# PDB.net
KiCad netlist of a schematic drawn in EAGLE
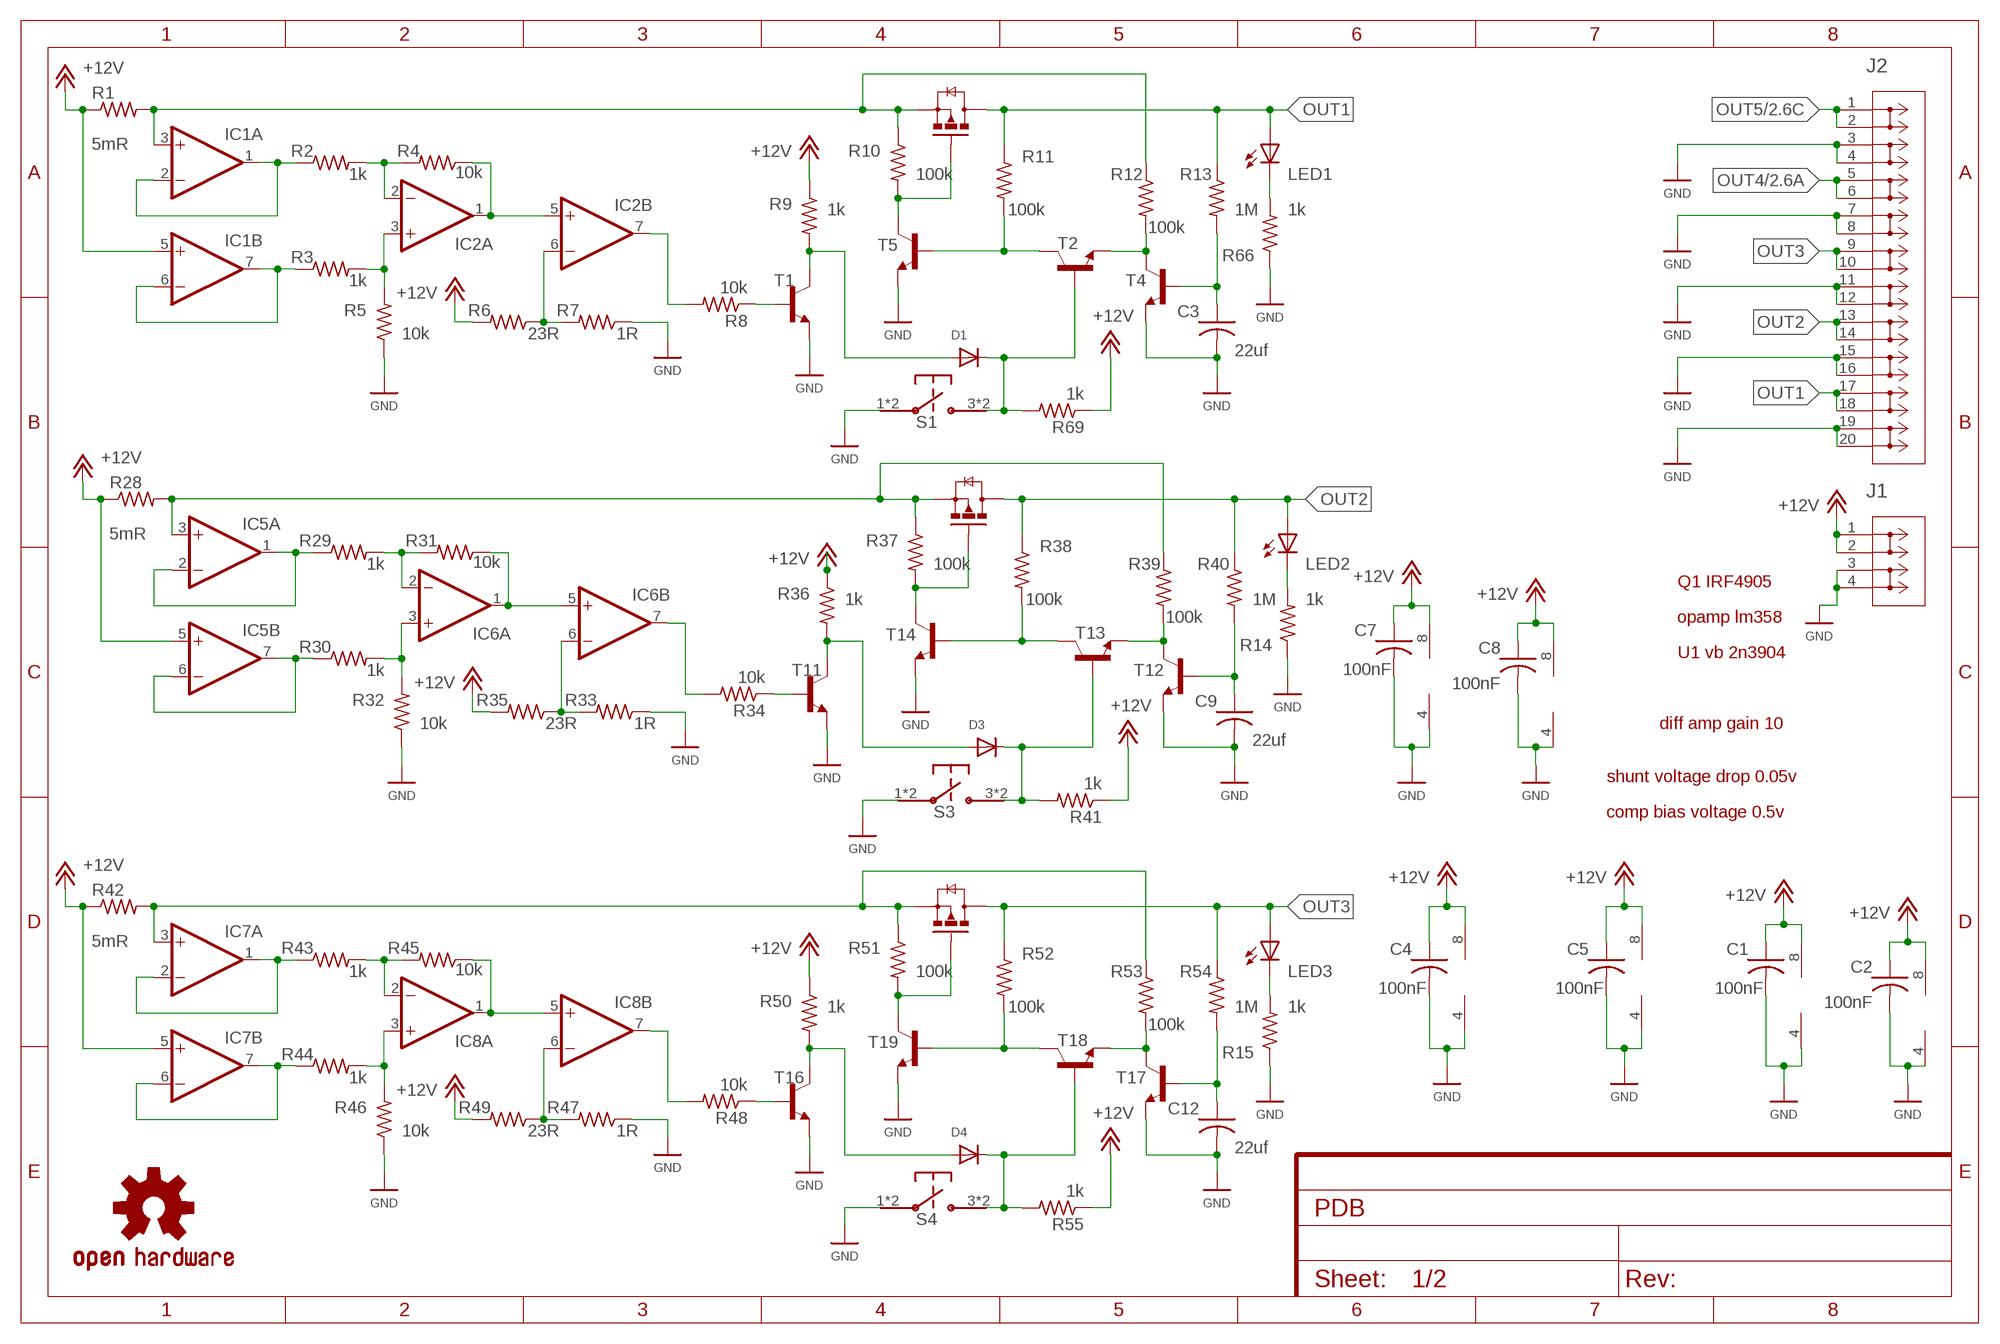
[diagram p0: schematic, sheet 1]
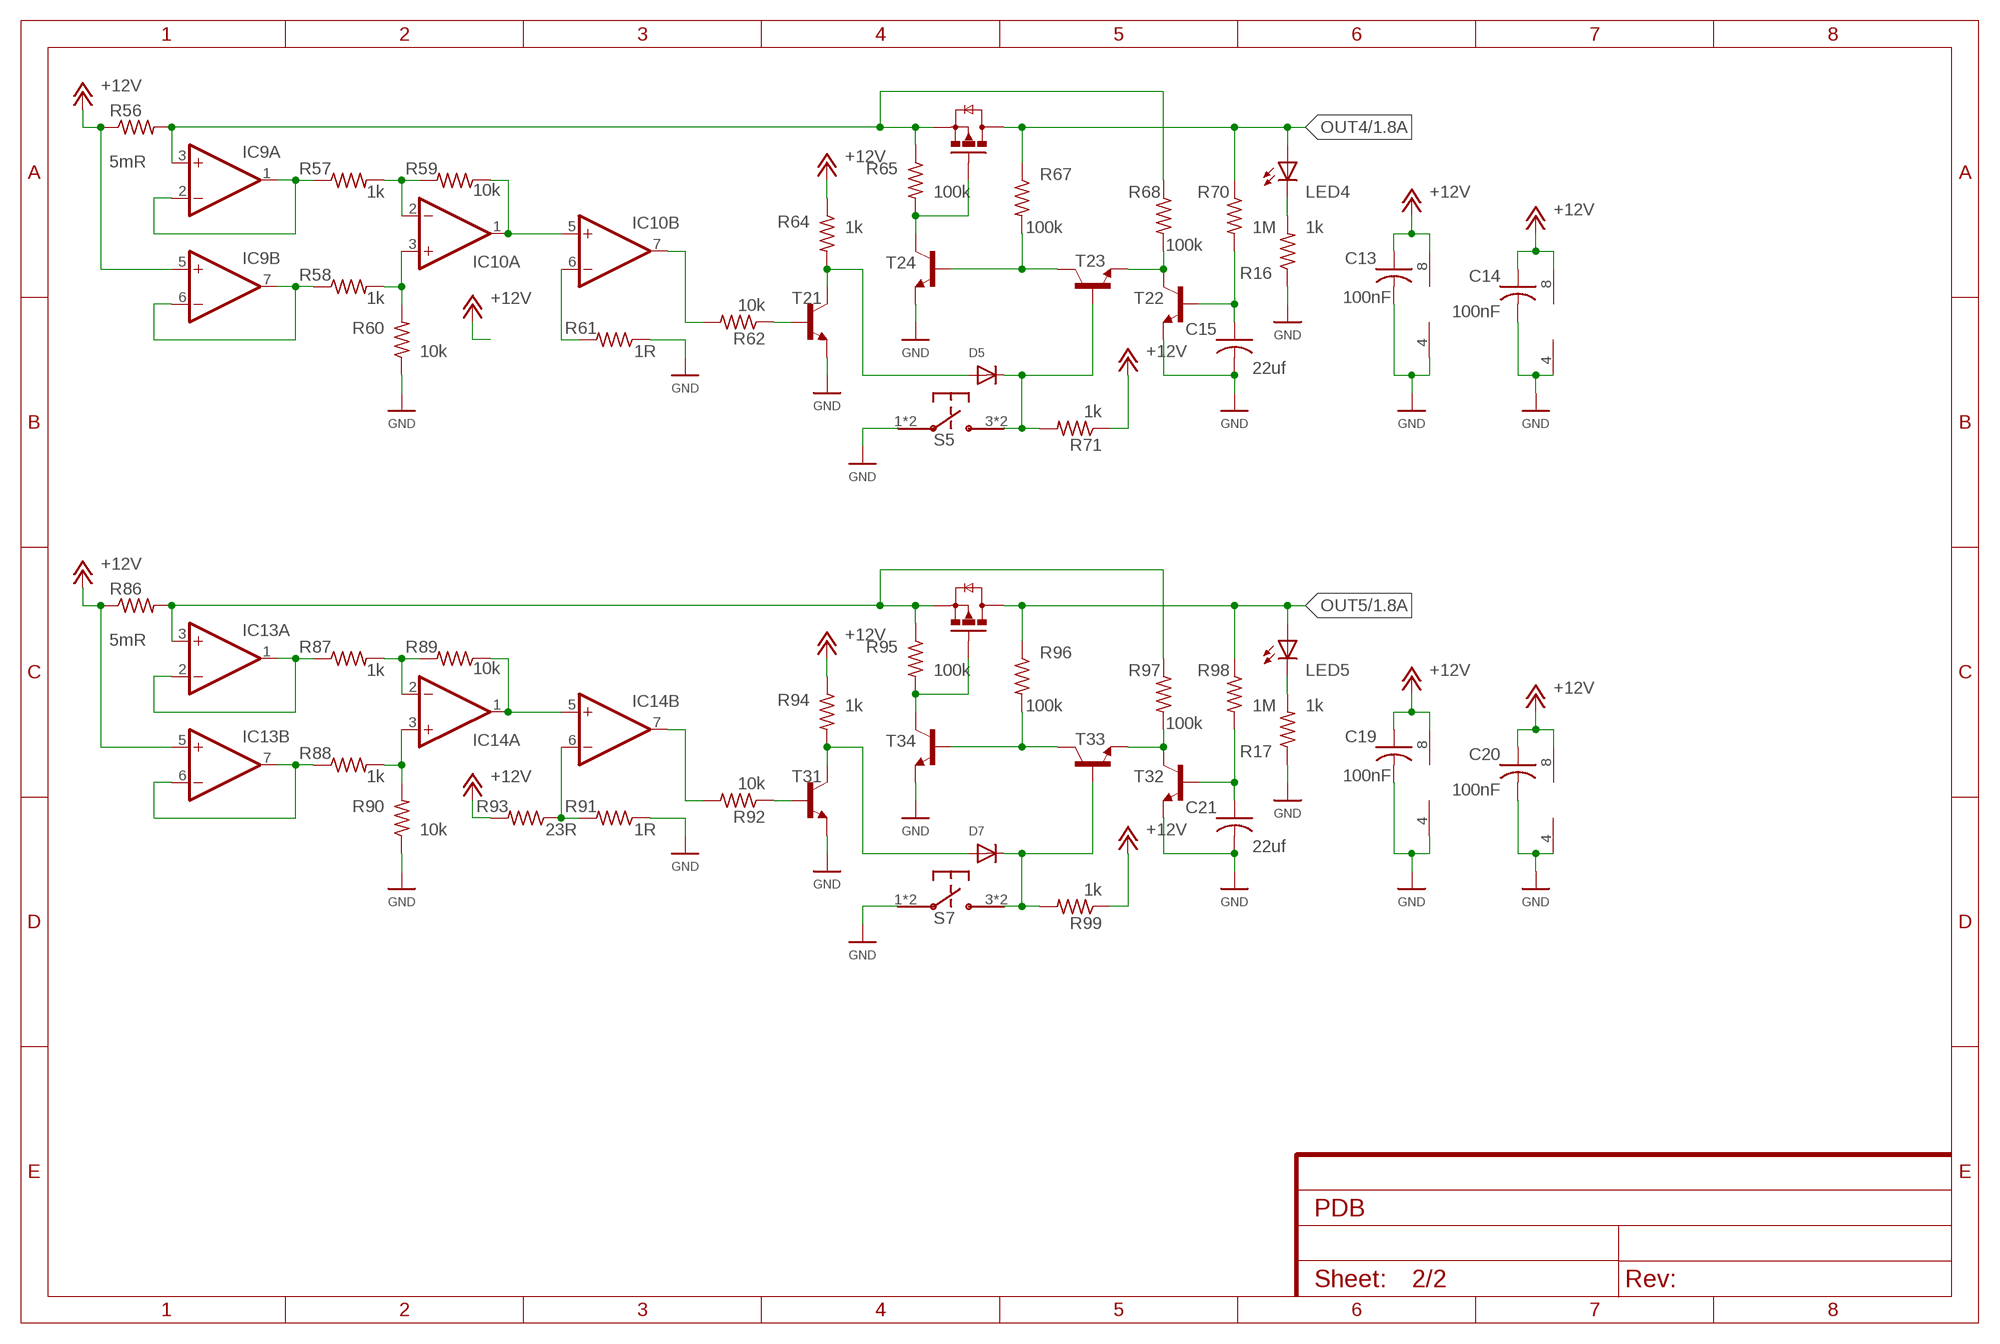
[diagram p1: schematic, sheet 2]

(export (version "E")
  (design (tool "Eeschema 10.0.6"))
  (components
    (comp (ref "C13")
      (value "100nF")
      (footprint "eagle-import:C0603")
      (libsource (lib "eagle-import") (part "C-USC0603"))
    )
    (comp (ref "C14")
      (value "100nF")
      (footprint "eagle-import:C0603")
      (libsource (lib "eagle-import") (part "C-USC0603"))
    )
    (comp (ref "C15")
      (value "22uf")
      (footprint "eagle-import:C0805")
      (libsource (lib "eagle-import") (part "C-USC0805"))
    )
    (comp (ref "C19")
      (value "100nF")
      (footprint "eagle-import:C0603")
      (libsource (lib "eagle-import") (part "C-USC0603"))
    )
    (comp (ref "C20")
      (value "100nF")
      (footprint "eagle-import:C0603")
      (libsource (lib "eagle-import") (part "C-USC0603"))
    )
    (comp (ref "C21")
      (value "22uf")
      (footprint "eagle-import:C0805")
      (libsource (lib "eagle-import") (part "C-USC0805"))
    )
    (comp (ref "D5")
      (value "DIODESOD-323F")
      (footprint "eagle-import:SOD-323F")
      (libsource (lib "eagle-import") (part "DIODESOD-323F"))
    )
    (comp (ref "D7")
      (value "DIODESOD-323F")
      (footprint "eagle-import:SOD-323F")
      (libsource (lib "eagle-import") (part "DIODESOD-323F"))
    )
    (comp (ref "IC9")
      (value "LM358D")
      (footprint "eagle-import:SO08")
      (libsource (lib "eagle-import") (part "LM358D"))
    )
    (comp (ref "IC10")
      (value "LM358D")
      (footprint "eagle-import:SO08")
      (libsource (lib "eagle-import") (part "LM358D"))
    )
    (comp (ref "IC13")
      (value "LM358D")
      (footprint "eagle-import:SO08")
      (libsource (lib "eagle-import") (part "LM358D"))
    )
    (comp (ref "IC14")
      (value "LM358D")
      (footprint "eagle-import:SO08")
      (libsource (lib "eagle-import") (part "LM358D"))
    )
    (comp (ref "LED4")
      (value "LEDCHIP-LED0603")
      (footprint "eagle-import:CHIP-LED0603")
      (libsource (lib "eagle-import") (part "LEDCHIP-LED0603"))
    )
    (comp (ref "LED5")
      (value "LEDCHIP-LED0603")
      (footprint "eagle-import:CHIP-LED0603")
      (libsource (lib "eagle-import") (part "LEDCHIP-LED0603"))
    )
    (comp (ref "R16")
      (value "1k")
      (footprint "eagle-import:R0603")
      (libsource (lib "eagle-import") (part "R-US_R0603"))
    )
    (comp (ref "R17")
      (value "1k")
      (footprint "eagle-import:R0603")
      (libsource (lib "eagle-import") (part "R-US_R0603"))
    )
    (comp (ref "R56")
      (value "5mR")
      (footprint "eagle-import:R2512")
      (libsource (lib "eagle-import") (part "R-US_R2512"))
    )
    (comp (ref "R57")
      (value "1k")
      (footprint "eagle-import:R0603")
      (libsource (lib "eagle-import") (part "R-US_R0603"))
    )
    (comp (ref "R58")
      (value "1k")
      (footprint "eagle-import:R0603")
      (libsource (lib "eagle-import") (part "R-US_R0603"))
    )
    (comp (ref "R59")
      (value "10k")
      (footprint "eagle-import:R0603")
      (libsource (lib "eagle-import") (part "R-US_R0603"))
    )
    (comp (ref "R60")
      (value "10k")
      (footprint "eagle-import:R0603")
      (libsource (lib "eagle-import") (part "R-US_R0603"))
    )
    (comp (ref "R61")
      (value "1R")
      (footprint "eagle-import:R0603")
      (libsource (lib "eagle-import") (part "R-US_R0603"))
    )
    (comp (ref "R62")
      (value "10k")
      (footprint "eagle-import:R0603")
      (libsource (lib "eagle-import") (part "R-US_R0603"))
    )
    (comp (ref "R64")
      (value "1k")
      (footprint "eagle-import:R0603")
      (libsource (lib "eagle-import") (part "R-US_R0603"))
    )
    (comp (ref "R65")
      (value "100k")
      (footprint "eagle-import:R0603")
      (libsource (lib "eagle-import") (part "R-US_R0603"))
    )
    (comp (ref "R67")
      (value "100k")
      (footprint "eagle-import:R0603")
      (libsource (lib "eagle-import") (part "R-US_R0603"))
    )
    (comp (ref "R68")
      (value "100k")
      (footprint "eagle-import:R0603")
      (libsource (lib "eagle-import") (part "R-US_R0603"))
    )
    (comp (ref "R70")
      (value "1M")
      (footprint "eagle-import:R0603")
      (libsource (lib "eagle-import") (part "R-US_R0603"))
    )
    (comp (ref "R71")
      (value "1k")
      (footprint "eagle-import:R0603")
      (libsource (lib "eagle-import") (part "R-US_R0603"))
    )
    (comp (ref "R86")
      (value "5mR")
      (footprint "eagle-import:R2512")
      (libsource (lib "eagle-import") (part "R-US_R2512"))
    )
    (comp (ref "R87")
      (value "1k")
      (footprint "eagle-import:R0603")
      (libsource (lib "eagle-import") (part "R-US_R0603"))
    )
    (comp (ref "R88")
      (value "1k")
      (footprint "eagle-import:R0603")
      (libsource (lib "eagle-import") (part "R-US_R0603"))
    )
    (comp (ref "R89")
      (value "10k")
      (footprint "eagle-import:R0603")
      (libsource (lib "eagle-import") (part "R-US_R0603"))
    )
    (comp (ref "R90")
      (value "10k")
      (footprint "eagle-import:R0603")
      (libsource (lib "eagle-import") (part "R-US_R0603"))
    )
    (comp (ref "R91")
      (value "1R")
      (footprint "eagle-import:R0603")
      (libsource (lib "eagle-import") (part "R-US_R0603"))
    )
    (comp (ref "R92")
      (value "10k")
      (footprint "eagle-import:R0603")
      (libsource (lib "eagle-import") (part "R-US_R0603"))
    )
    (comp (ref "R93")
      (value "23R")
      (footprint "eagle-import:R0603")
      (libsource (lib "eagle-import") (part "R-US_R0603"))
    )
    (comp (ref "R94")
      (value "1k")
      (footprint "eagle-import:R0603")
      (libsource (lib "eagle-import") (part "R-US_R0603"))
    )
    (comp (ref "R95")
      (value "100k")
      (footprint "eagle-import:R0603")
      (libsource (lib "eagle-import") (part "R-US_R0603"))
    )
    (comp (ref "R96")
      (value "100k")
      (footprint "eagle-import:R0603")
      (libsource (lib "eagle-import") (part "R-US_R0603"))
    )
    (comp (ref "R97")
      (value "100k")
      (footprint "eagle-import:R0603")
      (libsource (lib "eagle-import") (part "R-US_R0603"))
    )
    (comp (ref "R98")
      (value "1M")
      (footprint "eagle-import:R0603")
      (libsource (lib "eagle-import") (part "R-US_R0603"))
    )
    (comp (ref "R99")
      (value "1k")
      (footprint "eagle-import:R0603")
      (libsource (lib "eagle-import") (part "R-US_R0603"))
    )
    (comp (ref "S5")
      (value "PTS645SM43SMTR")
      (footprint "eagle-import:PTS645SM43SMTR")
      (libsource (lib "eagle-import") (part "PTS645SM43SMTR"))
    )
    (comp (ref "S7")
      (value "PTS645SM43SMTR")
      (footprint "eagle-import:PTS645SM43SMTR")
      (libsource (lib "eagle-import") (part "PTS645SM43SMTR"))
    )
    (comp (ref "T21")
      (value "2N3904SMD")
      (footprint "eagle-import:SOT23-BACKUP")
      (libsource (lib "eagle-import") (part "2N3904SMD"))
    )
    (comp (ref "T22")
      (value "2N3904SMD")
      (footprint "eagle-import:SOT23-BACKUP")
      (libsource (lib "eagle-import") (part "2N3904SMD"))
    )
    (comp (ref "T23")
      (value "2N3904SMD")
      (footprint "eagle-import:SOT23-BACKUP")
      (libsource (lib "eagle-import") (part "2N3904SMD"))
    )
    (comp (ref "T24")
      (value "2N3904SMD")
      (footprint "eagle-import:SOT23-BACKUP")
      (libsource (lib "eagle-import") (part "2N3904SMD"))
    )
    (comp (ref "T25")
      (value "IRF4905")
      (footprint "eagle-import:TO263-3")
      (libsource (lib "eagle-import") (part "IRF4905"))
    )
    (comp (ref "T31")
      (value "2N3904SMD")
      (footprint "eagle-import:SOT23-BACKUP")
      (libsource (lib "eagle-import") (part "2N3904SMD"))
    )
    (comp (ref "T32")
      (value "2N3904SMD")
      (footprint "eagle-import:SOT23-BACKUP")
      (libsource (lib "eagle-import") (part "2N3904SMD"))
    )
    (comp (ref "T33")
      (value "2N3904SMD")
      (footprint "eagle-import:SOT23-BACKUP")
      (libsource (lib "eagle-import") (part "2N3904SMD"))
    )
    (comp (ref "T34")
      (value "2N3904SMD")
      (footprint "eagle-import:SOT23-BACKUP")
      (libsource (lib "eagle-import") (part "2N3904SMD"))
    )
    (comp (ref "T35")
      (value "IRF4905")
      (footprint "eagle-import:TO263-3")
      (libsource (lib "eagle-import") (part "IRF4905"))
    )
    (comp (ref "C1")
      (value "100nF")
      (footprint "eagle-import:C0603")
      (libsource (lib "eagle-import") (part "C-USC0603"))
    )
    (comp (ref "C2")
      (value "100nF")
      (footprint "eagle-import:C0603")
      (libsource (lib "eagle-import") (part "C-USC0603"))
    )
    (comp (ref "C3")
      (value "22uf")
      (footprint "eagle-import:C0805")
      (libsource (lib "eagle-import") (part "C-USC0805"))
    )
    (comp (ref "C4")
      (value "100nF")
      (footprint "eagle-import:C0603")
      (libsource (lib "eagle-import") (part "C-USC0603"))
    )
    (comp (ref "C5")
      (value "100nF")
      (footprint "eagle-import:C0603")
      (libsource (lib "eagle-import") (part "C-USC0603"))
    )
    (comp (ref "C7")
      (value "100nF")
      (footprint "eagle-import:C0603")
      (libsource (lib "eagle-import") (part "C-USC0603"))
    )
    (comp (ref "C8")
      (value "100nF")
      (footprint "eagle-import:C0603")
      (libsource (lib "eagle-import") (part "C-USC0603"))
    )
    (comp (ref "C9")
      (value "22uf")
      (footprint "eagle-import:C0805")
      (libsource (lib "eagle-import") (part "C-USC0805"))
    )
    (comp (ref "C12")
      (value "22uf")
      (footprint "eagle-import:C0805")
      (libsource (lib "eagle-import") (part "C-USC0805"))
    )
    (comp (ref "D1")
      (value "DIODESOD-323F")
      (footprint "eagle-import:SOD-323F")
      (libsource (lib "eagle-import") (part "DIODESOD-323F"))
    )
    (comp (ref "D3")
      (value "DIODESOD-323F")
      (footprint "eagle-import:SOD-323F")
      (libsource (lib "eagle-import") (part "DIODESOD-323F"))
    )
    (comp (ref "D4")
      (value "DIODESOD-323F")
      (footprint "eagle-import:SOD-323F")
      (libsource (lib "eagle-import") (part "DIODESOD-323F"))
    )
    (comp (ref "IC1")
      (value "LM358D")
      (footprint "eagle-import:SO08")
      (libsource (lib "eagle-import") (part "LM358D"))
    )
    (comp (ref "IC2")
      (value "LM358D")
      (footprint "eagle-import:SO08")
      (libsource (lib "eagle-import") (part "LM358D"))
    )
    (comp (ref "IC5")
      (value "LM358D")
      (footprint "eagle-import:SO08")
      (libsource (lib "eagle-import") (part "LM358D"))
    )
    (comp (ref "IC6")
      (value "LM358D")
      (footprint "eagle-import:SO08")
      (libsource (lib "eagle-import") (part "LM358D"))
    )
    (comp (ref "IC7")
      (value "LM358D")
      (footprint "eagle-import:SO08")
      (libsource (lib "eagle-import") (part "LM358D"))
    )
    (comp (ref "IC8")
      (value "LM358D")
      (footprint "eagle-import:SO08")
      (libsource (lib "eagle-import") (part "LM358D"))
    )
    (comp (ref "J1")
      (value "2606-1102")
      (footprint "eagle-import:CONN2_2606-1102_WAG")
      (fields (field (name "COPYRIGHT") "Copyright (C) 2024 Ultra Librarian. All rights reserved."))
      (libsource (lib "eagle-import") (part "2606-1102"))
    )
    (comp (ref "J2")
      (value "2604-1110")
      (footprint "eagle-import:CONN10_2604-1110_WAG")
      (fields (field (name "COPYRIGHT") "Copyright (C) 2024 Ultra Librarian. All rights reserved."))
      (libsource (lib "eagle-import") (part "2604-1110"))
    )
    (comp (ref "LED1")
      (value "LEDCHIP-LED0603")
      (footprint "eagle-import:CHIP-LED0603")
      (libsource (lib "eagle-import") (part "LEDCHIP-LED0603"))
    )
    (comp (ref "LED2")
      (value "LEDCHIP-LED0603")
      (footprint "eagle-import:CHIP-LED0603")
      (libsource (lib "eagle-import") (part "LEDCHIP-LED0603"))
    )
    (comp (ref "LED3")
      (value "LEDCHIP-LED0603")
      (footprint "eagle-import:CHIP-LED0603")
      (libsource (lib "eagle-import") (part "LEDCHIP-LED0603"))
    )
    (comp (ref "LOGO1")
      (value "OSHW-LOGOL")
      (footprint "eagle-import:OSHW-LOGO-L")
      (libsource (lib "eagle-import") (part "OSHW-LOGOL"))
    )
    (comp (ref "R1")
      (value "5mR")
      (footprint "eagle-import:R2512")
      (libsource (lib "eagle-import") (part "R-US_R2512"))
    )
    (comp (ref "R2")
      (value "1k")
      (footprint "eagle-import:R0603")
      (libsource (lib "eagle-import") (part "R-US_R0603"))
    )
    (comp (ref "R3")
      (value "1k")
      (footprint "eagle-import:R0603")
      (libsource (lib "eagle-import") (part "R-US_R0603"))
    )
    (comp (ref "R4")
      (value "10k")
      (footprint "eagle-import:R0603")
      (libsource (lib "eagle-import") (part "R-US_R0603"))
    )
    (comp (ref "R5")
      (value "10k")
      (footprint "eagle-import:R0603")
      (libsource (lib "eagle-import") (part "R-US_R0603"))
    )
    (comp (ref "R6")
      (value "23R")
      (footprint "eagle-import:R0603")
      (libsource (lib "eagle-import") (part "R-US_R0603"))
    )
    (comp (ref "R7")
      (value "1R")
      (footprint "eagle-import:R0603")
      (libsource (lib "eagle-import") (part "R-US_R0603"))
    )
    (comp (ref "R8")
      (value "10k")
      (footprint "eagle-import:R0603")
      (libsource (lib "eagle-import") (part "R-US_R0603"))
    )
    (comp (ref "R9")
      (value "1k")
      (footprint "eagle-import:R0603")
      (libsource (lib "eagle-import") (part "R-US_R0603"))
    )
    (comp (ref "R10")
      (value "100k")
      (footprint "eagle-import:R0603")
      (libsource (lib "eagle-import") (part "R-US_R0603"))
    )
    (comp (ref "R11")
      (value "100k")
      (footprint "eagle-import:R0603")
      (libsource (lib "eagle-import") (part "R-US_R0603"))
    )
    (comp (ref "R12")
      (value "100k")
      (footprint "eagle-import:R0603")
      (libsource (lib "eagle-import") (part "R-US_R0603"))
    )
    (comp (ref "R13")
      (value "1M")
      (footprint "eagle-import:R0603")
      (libsource (lib "eagle-import") (part "R-US_R0603"))
    )
    (comp (ref "R14")
      (value "1k")
      (footprint "eagle-import:R0603")
      (libsource (lib "eagle-import") (part "R-US_R0603"))
    )
    (comp (ref "R15")
      (value "1k")
      (footprint "eagle-import:R0603")
      (libsource (lib "eagle-import") (part "R-US_R0603"))
    )
    (comp (ref "R28")
      (value "5mR")
      (footprint "eagle-import:R2512")
      (libsource (lib "eagle-import") (part "R-US_R2512"))
    )
    (comp (ref "R29")
      (value "1k")
      (footprint "eagle-import:R0603")
      (libsource (lib "eagle-import") (part "R-US_R0603"))
    )
    (comp (ref "R30")
      (value "1k")
      (footprint "eagle-import:R0603")
      (libsource (lib "eagle-import") (part "R-US_R0603"))
    )
    (comp (ref "R31")
      (value "10k")
      (footprint "eagle-import:R0603")
      (libsource (lib "eagle-import") (part "R-US_R0603"))
    )
    (comp (ref "R32")
      (value "10k")
      (footprint "eagle-import:R0603")
      (libsource (lib "eagle-import") (part "R-US_R0603"))
    )
    (comp (ref "R33")
      (value "1R")
      (footprint "eagle-import:R0603")
      (libsource (lib "eagle-import") (part "R-US_R0603"))
    )
    (comp (ref "R34")
      (value "10k")
      (footprint "eagle-import:R0603")
      (libsource (lib "eagle-import") (part "R-US_R0603"))
    )
    (comp (ref "R35")
      (value "23R")
      (footprint "eagle-import:R0603")
      (libsource (lib "eagle-import") (part "R-US_R0603"))
    )
    (comp (ref "R36")
      (value "1k")
      (footprint "eagle-import:R0603")
      (libsource (lib "eagle-import") (part "R-US_R0603"))
    )
    (comp (ref "R37")
      (value "100k")
      (footprint "eagle-import:R0603")
      (libsource (lib "eagle-import") (part "R-US_R0603"))
    )
    (comp (ref "R38")
      (value "100k")
      (footprint "eagle-import:R0603")
      (libsource (lib "eagle-import") (part "R-US_R0603"))
    )
    (comp (ref "R39")
      (value "100k")
      (footprint "eagle-import:R0603")
      (libsource (lib "eagle-import") (part "R-US_R0603"))
    )
    (comp (ref "R40")
      (value "1M")
      (footprint "eagle-import:R0603")
      (libsource (lib "eagle-import") (part "R-US_R0603"))
    )
    (comp (ref "R41")
      (value "1k")
      (footprint "eagle-import:R0603")
      (libsource (lib "eagle-import") (part "R-US_R0603"))
    )
    (comp (ref "R42")
      (value "5mR")
      (footprint "eagle-import:R2512")
      (libsource (lib "eagle-import") (part "R-US_R2512"))
    )
    (comp (ref "R43")
      (value "1k")
      (footprint "eagle-import:R0603")
      (libsource (lib "eagle-import") (part "R-US_R0603"))
    )
    (comp (ref "R44")
      (value "1k")
      (footprint "eagle-import:R0603")
      (libsource (lib "eagle-import") (part "R-US_R0603"))
    )
    (comp (ref "R45")
      (value "10k")
      (footprint "eagle-import:R0603")
      (libsource (lib "eagle-import") (part "R-US_R0603"))
    )
    (comp (ref "R46")
      (value "10k")
      (footprint "eagle-import:R0603")
      (libsource (lib "eagle-import") (part "R-US_R0603"))
    )
    (comp (ref "R47")
      (value "1R")
      (footprint "eagle-import:R0603")
      (libsource (lib "eagle-import") (part "R-US_R0603"))
    )
    (comp (ref "R48")
      (value "10k")
      (footprint "eagle-import:R0603")
      (libsource (lib "eagle-import") (part "R-US_R0603"))
    )
    (comp (ref "R49")
      (value "23R")
      (footprint "eagle-import:R0603")
      (libsource (lib "eagle-import") (part "R-US_R0603"))
    )
    (comp (ref "R50")
      (value "1k")
      (footprint "eagle-import:R0603")
      (libsource (lib "eagle-import") (part "R-US_R0603"))
    )
    (comp (ref "R51")
      (value "100k")
      (footprint "eagle-import:R0603")
      (libsource (lib "eagle-import") (part "R-US_R0603"))
    )
    (comp (ref "R52")
      (value "100k")
      (footprint "eagle-import:R0603")
      (libsource (lib "eagle-import") (part "R-US_R0603"))
    )
    (comp (ref "R53")
      (value "100k")
      (footprint "eagle-import:R0603")
      (libsource (lib "eagle-import") (part "R-US_R0603"))
    )
    (comp (ref "R54")
      (value "1M")
      (footprint "eagle-import:R0603")
      (libsource (lib "eagle-import") (part "R-US_R0603"))
    )
    (comp (ref "R55")
      (value "1k")
      (footprint "eagle-import:R0603")
      (libsource (lib "eagle-import") (part "R-US_R0603"))
    )
    (comp (ref "R66")
      (value "1k")
      (footprint "eagle-import:R0603")
      (libsource (lib "eagle-import") (part "R-US_R0603"))
    )
    (comp (ref "R69")
      (value "1k")
      (footprint "eagle-import:R0603")
      (libsource (lib "eagle-import") (part "R-US_R0603"))
    )
    (comp (ref "S1")
      (value "PTS645SM43SMTR")
      (footprint "eagle-import:PTS645SM43SMTR")
      (libsource (lib "eagle-import") (part "PTS645SM43SMTR"))
    )
    (comp (ref "S3")
      (value "PTS645SM43SMTR")
      (footprint "eagle-import:PTS645SM43SMTR")
      (libsource (lib "eagle-import") (part "PTS645SM43SMTR"))
    )
    (comp (ref "S4")
      (value "PTS645SM43SMTR")
      (footprint "eagle-import:PTS645SM43SMTR")
      (libsource (lib "eagle-import") (part "PTS645SM43SMTR"))
    )
    (comp (ref "T1")
      (value "2N3904SMD")
      (footprint "eagle-import:SOT23-BACKUP")
      (libsource (lib "eagle-import") (part "2N3904SMD"))
    )
    (comp (ref "T2")
      (value "2N3904SMD")
      (footprint "eagle-import:SOT23-BACKUP")
      (libsource (lib "eagle-import") (part "2N3904SMD"))
    )
    (comp (ref "T3")
      (value "IRF4905")
      (footprint "eagle-import:TO263-3")
      (libsource (lib "eagle-import") (part "IRF4905"))
    )
    (comp (ref "T4")
      (value "2N3904SMD")
      (footprint "eagle-import:SOT23-BACKUP")
      (libsource (lib "eagle-import") (part "2N3904SMD"))
    )
    (comp (ref "T5")
      (value "2N3904SMD")
      (footprint "eagle-import:SOT23-BACKUP")
      (libsource (lib "eagle-import") (part "2N3904SMD"))
    )
    (comp (ref "T11")
      (value "2N3904SMD")
      (footprint "eagle-import:SOT23-BACKUP")
      (libsource (lib "eagle-import") (part "2N3904SMD"))
    )
    (comp (ref "T12")
      (value "2N3904SMD")
      (footprint "eagle-import:SOT23-BACKUP")
      (libsource (lib "eagle-import") (part "2N3904SMD"))
    )
    (comp (ref "T13")
      (value "2N3904SMD")
      (footprint "eagle-import:SOT23-BACKUP")
      (libsource (lib "eagle-import") (part "2N3904SMD"))
    )
    (comp (ref "T14")
      (value "2N3904SMD")
      (footprint "eagle-import:SOT23-BACKUP")
      (libsource (lib "eagle-import") (part "2N3904SMD"))
    )
    (comp (ref "T15")
      (value "IRF4905")
      (footprint "eagle-import:TO263-3")
      (libsource (lib "eagle-import") (part "IRF4905"))
    )
    (comp (ref "T16")
      (value "2N3904SMD")
      (footprint "eagle-import:SOT23-BACKUP")
      (libsource (lib "eagle-import") (part "2N3904SMD"))
    )
    (comp (ref "T17")
      (value "2N3904SMD")
      (footprint "eagle-import:SOT23-BACKUP")
      (libsource (lib "eagle-import") (part "2N3904SMD"))
    )
    (comp (ref "T18")
      (value "2N3904SMD")
      (footprint "eagle-import:SOT23-BACKUP")
      (libsource (lib "eagle-import") (part "2N3904SMD"))
    )
    (comp (ref "T19")
      (value "2N3904SMD")
      (footprint "eagle-import:SOT23-BACKUP")
      (libsource (lib "eagle-import") (part "2N3904SMD"))
    )
    (comp (ref "T20")
      (value "IRF4905")
      (footprint "eagle-import:TO263-3")
      (libsource (lib "eagle-import") (part "IRF4905"))
    )
  )
  (nets
    (net (code "1") (name "+12V") (class "Default")
      (node (ref "C1") (pin "1") (pinfunction "1_1") (pintype "passive"))
      (node (ref "C13") (pin "1") (pinfunction "1_1") (pintype "passive"))
      (node (ref "C14") (pin "1") (pinfunction "1_1") (pintype "passive"))
      (node (ref "C19") (pin "1") (pinfunction "1_1") (pintype "passive"))
      (node (ref "C2") (pin "1") (pinfunction "1_1") (pintype "passive"))
      (node (ref "C20") (pin "1") (pinfunction "1_1") (pintype "passive"))
      (node (ref "C4") (pin "1") (pinfunction "1_1") (pintype "passive"))
      (node (ref "C5") (pin "1") (pinfunction "1_1") (pintype "passive"))
      (node (ref "C7") (pin "1") (pinfunction "1_1") (pintype "passive"))
      (node (ref "C8") (pin "1") (pinfunction "1_1") (pintype "passive"))
      (node (ref "IC1") (pin "5") (pinfunction "+IN_5") (pintype "input"))
      (node (ref "IC1") (pin "8") (pinfunction "V+_8") (pintype "power_in"))
      (node (ref "IC10") (pin "8") (pinfunction "V+_8") (pintype "power_in"))
      (node (ref "IC13") (pin "5") (pinfunction "+IN_5") (pintype "input"))
      (node (ref "IC13") (pin "8") (pinfunction "V+_8") (pintype "power_in"))
      (node (ref "IC14") (pin "8") (pinfunction "V+_8") (pintype "power_in"))
      (node (ref "IC2") (pin "8") (pinfunction "V+_8") (pintype "power_in"))
      (node (ref "IC5") (pin "5") (pinfunction "+IN_5") (pintype "input"))
      (node (ref "IC5") (pin "8") (pinfunction "V+_8") (pintype "power_in"))
      (node (ref "IC6") (pin "8") (pinfunction "V+_8") (pintype "power_in"))
      (node (ref "IC7") (pin "5") (pinfunction "+IN_5") (pintype "input"))
      (node (ref "IC7") (pin "8") (pinfunction "V+_8") (pintype "power_in"))
      (node (ref "IC8") (pin "8") (pinfunction "V+_8") (pintype "power_in"))
      (node (ref "IC9") (pin "5") (pinfunction "+IN_5") (pintype "input"))
      (node (ref "IC9") (pin "8") (pinfunction "V+_8") (pintype "power_in"))
      (node (ref "J1") (pin "1") (pinfunction "1_1_1") (pintype "passive"))
      (node (ref "J1") (pin "2") (pinfunction "1_2_2") (pintype "passive"))
      (node (ref "R1") (pin "1") (pinfunction "1_1") (pintype "passive"))
      (node (ref "R28") (pin "1") (pinfunction "1_1") (pintype "passive"))
      (node (ref "R35") (pin "2") (pinfunction "2_2") (pintype "passive"))
      (node (ref "R36") (pin "1") (pinfunction "1_1") (pintype "passive"))
      (node (ref "R41") (pin "1") (pinfunction "1_1") (pintype "passive"))
      (node (ref "R42") (pin "1") (pinfunction "1_1") (pintype "passive"))
      (node (ref "R49") (pin "2") (pinfunction "2_2") (pintype "passive"))
      (node (ref "R50") (pin "1") (pinfunction "1_1") (pintype "passive"))
      (node (ref "R55") (pin "1") (pinfunction "1_1") (pintype "passive"))
      (node (ref "R56") (pin "1") (pinfunction "1_1") (pintype "passive"))
      (node (ref "R6") (pin "2") (pinfunction "2_2") (pintype "passive"))
      (node (ref "R64") (pin "1") (pinfunction "1_1") (pintype "passive"))
      (node (ref "R69") (pin "1") (pinfunction "1_1") (pintype "passive"))
      (node (ref "R71") (pin "1") (pinfunction "1_1") (pintype "passive"))
      (node (ref "R86") (pin "1") (pinfunction "1_1") (pintype "passive"))
      (node (ref "R9") (pin "1") (pinfunction "1_1") (pintype "passive"))
      (node (ref "R93") (pin "2") (pinfunction "2_2") (pintype "passive"))
      (node (ref "R94") (pin "1") (pinfunction "1_1") (pintype "passive"))
      (node (ref "R99") (pin "1") (pinfunction "1_1") (pintype "passive"))
    )
    (net (code "2") (name "GND") (class "Default")
      (node (ref "C1") (pin "2") (pinfunction "2_2") (pintype "passive"))
      (node (ref "C12") (pin "2") (pinfunction "2_2") (pintype "passive"))
      (node (ref "C13") (pin "2") (pinfunction "2_2") (pintype "passive"))
      (node (ref "C14") (pin "2") (pinfunction "2_2") (pintype "passive"))
      (node (ref "C15") (pin "2") (pinfunction "2_2") (pintype "passive"))
      (node (ref "C19") (pin "2") (pinfunction "2_2") (pintype "passive"))
      (node (ref "C2") (pin "2") (pinfunction "2_2") (pintype "passive"))
      (node (ref "C20") (pin "2") (pinfunction "2_2") (pintype "passive"))
      (node (ref "C21") (pin "2") (pinfunction "2_2") (pintype "passive"))
      (node (ref "C3") (pin "2") (pinfunction "2_2") (pintype "passive"))
      (node (ref "C4") (pin "2") (pinfunction "2_2") (pintype "passive"))
      (node (ref "C5") (pin "2") (pinfunction "2_2") (pintype "passive"))
      (node (ref "C7") (pin "2") (pinfunction "2_2") (pintype "passive"))
      (node (ref "C8") (pin "2") (pinfunction "2_2") (pintype "passive"))
      (node (ref "C9") (pin "2") (pinfunction "2_2") (pintype "passive"))
      (node (ref "IC1") (pin "4") (pinfunction "V-_4") (pintype "power_in"))
      (node (ref "IC10") (pin "4") (pinfunction "V-_4") (pintype "power_in"))
      (node (ref "IC13") (pin "4") (pinfunction "V-_4") (pintype "power_in"))
      (node (ref "IC14") (pin "4") (pinfunction "V-_4") (pintype "power_in"))
      (node (ref "IC2") (pin "4") (pinfunction "V-_4") (pintype "power_in"))
      (node (ref "IC5") (pin "4") (pinfunction "V-_4") (pintype "power_in"))
      (node (ref "IC6") (pin "4") (pinfunction "V-_4") (pintype "power_in"))
      (node (ref "IC7") (pin "4") (pinfunction "V-_4") (pintype "power_in"))
      (node (ref "IC8") (pin "4") (pinfunction "V-_4") (pintype "power_in"))
      (node (ref "IC9") (pin "4") (pinfunction "V-_4") (pintype "power_in"))
      (node (ref "J1") (pin "3") (pinfunction "2_1_3") (pintype "passive"))
      (node (ref "J1") (pin "4") (pinfunction "2_2_4") (pintype "passive"))
      (node (ref "J2") (pin "11") (pinfunction "6_1_11") (pintype "passive"))
      (node (ref "J2") (pin "12") (pinfunction "6_2_12") (pintype "passive"))
      (node (ref "J2") (pin "15") (pinfunction "8_1_15") (pintype "passive"))
      (node (ref "J2") (pin "16") (pinfunction "8_2_16") (pintype "passive"))
      (node (ref "J2") (pin "19") (pinfunction "10_1_19") (pintype "passive"))
      (node (ref "J2") (pin "20") (pinfunction "10_2_20") (pintype "passive"))
      (node (ref "J2") (pin "3") (pinfunction "2_1_3") (pintype "passive"))
      (node (ref "J2") (pin "4") (pinfunction "2_2_4") (pintype "passive"))
      (node (ref "J2") (pin "7") (pinfunction "4_1_7") (pintype "passive"))
      (node (ref "J2") (pin "8") (pinfunction "4_2_8") (pintype "passive"))
      (node (ref "R14") (pin "1") (pinfunction "1_1") (pintype "passive"))
      (node (ref "R15") (pin "1") (pinfunction "1_1") (pintype "passive"))
      (node (ref "R16") (pin "1") (pinfunction "1_1") (pintype "passive"))
      (node (ref "R17") (pin "1") (pinfunction "1_1") (pintype "passive"))
      (node (ref "R32") (pin "1") (pinfunction "1_1") (pintype "passive"))
      (node (ref "R33") (pin "1") (pinfunction "1_1") (pintype "passive"))
      (node (ref "R46") (pin "1") (pinfunction "1_1") (pintype "passive"))
      (node (ref "R47") (pin "1") (pinfunction "1_1") (pintype "passive"))
      (node (ref "R5") (pin "1") (pinfunction "1_1") (pintype "passive"))
      (node (ref "R60") (pin "1") (pinfunction "1_1") (pintype "passive"))
      (node (ref "R61") (pin "1") (pinfunction "1_1") (pintype "passive"))
      (node (ref "R66") (pin "1") (pinfunction "1_1") (pintype "passive"))
      (node (ref "R7") (pin "1") (pinfunction "1_1") (pintype "passive"))
      (node (ref "R90") (pin "1") (pinfunction "1_1") (pintype "passive"))
      (node (ref "R91") (pin "1") (pinfunction "1_1") (pintype "passive"))
      (node (ref "S1") (pin "1") (pinfunction "P$1_1") (pintype "passive"))
      (node (ref "S1") (pin "2") (pinfunction "P$1_2") (pintype "passive"))
      (node (ref "S3") (pin "1") (pinfunction "P$1_1") (pintype "passive"))
      (node (ref "S3") (pin "2") (pinfunction "P$1_2") (pintype "passive"))
      (node (ref "S4") (pin "1") (pinfunction "P$1_1") (pintype "passive"))
      (node (ref "S4") (pin "2") (pinfunction "P$1_2") (pintype "passive"))
      (node (ref "S5") (pin "1") (pinfunction "P$1_1") (pintype "passive"))
      (node (ref "S5") (pin "2") (pinfunction "P$1_2") (pintype "passive"))
      (node (ref "S7") (pin "1") (pinfunction "P$1_1") (pintype "passive"))
      (node (ref "S7") (pin "2") (pinfunction "P$1_2") (pintype "passive"))
      (node (ref "T1") (pin "2") (pinfunction "E_2") (pintype "passive"))
      (node (ref "T11") (pin "2") (pinfunction "E_2") (pintype "passive"))
      (node (ref "T12") (pin "2") (pinfunction "E_2") (pintype "passive"))
      (node (ref "T14") (pin "2") (pinfunction "E_2") (pintype "passive"))
      (node (ref "T16") (pin "2") (pinfunction "E_2") (pintype "passive"))
      (node (ref "T17") (pin "2") (pinfunction "E_2") (pintype "passive"))
      (node (ref "T19") (pin "2") (pinfunction "E_2") (pintype "passive"))
      (node (ref "T21") (pin "2") (pinfunction "E_2") (pintype "passive"))
      (node (ref "T22") (pin "2") (pinfunction "E_2") (pintype "passive"))
      (node (ref "T24") (pin "2") (pinfunction "E_2") (pintype "passive"))
      (node (ref "T31") (pin "2") (pinfunction "E_2") (pintype "passive"))
      (node (ref "T32") (pin "2") (pinfunction "E_2") (pintype "passive"))
      (node (ref "T34") (pin "2") (pinfunction "E_2") (pintype "passive"))
      (node (ref "T4") (pin "2") (pinfunction "E_2") (pintype "passive"))
      (node (ref "T5") (pin "2") (pinfunction "E_2") (pintype "passive"))
    )
    (net (code "3") (name "Net-(IC1A-+IN)") (class "Default")
      (node (ref "IC1") (pin "3") (pinfunction "+IN_3") (pintype "input"))
      (node (ref "R1") (pin "2") (pinfunction "2_2") (pintype "passive"))
      (node (ref "R10") (pin "1") (pinfunction "1_1") (pintype "passive"))
      (node (ref "R12") (pin "1") (pinfunction "1_1") (pintype "passive"))
      (node (ref "T3") (pin "3") (pinfunction "S_3") (pintype "passive"))
    )
    (net (code "4") (name "Net-(IC1A--IN)") (class "Default")
      (node (ref "IC1") (pin "1") (pinfunction "OUT_1") (pintype "output"))
      (node (ref "IC1") (pin "2") (pinfunction "-IN_2") (pintype "input"))
      (node (ref "R2") (pin "1") (pinfunction "1_1") (pintype "passive"))
    )
    (net (code "5") (name "Net-(IC1B--IN)") (class "Default")
      (node (ref "IC1") (pin "6") (pinfunction "-IN_6") (pintype "input"))
      (node (ref "IC1") (pin "7") (pinfunction "OUT_7") (pintype "output"))
      (node (ref "R3") (pin "1") (pinfunction "1_1") (pintype "passive"))
    )
    (net (code "6") (name "Net-(IC2A-+IN)") (class "Default")
      (node (ref "IC2") (pin "3") (pinfunction "+IN_3") (pintype "input"))
      (node (ref "R3") (pin "2") (pinfunction "2_2") (pintype "passive"))
      (node (ref "R5") (pin "2") (pinfunction "2_2") (pintype "passive"))
    )
    (net (code "7") (name "Net-(IC2A--IN)") (class "Default")
      (node (ref "IC2") (pin "2") (pinfunction "-IN_2") (pintype "input"))
      (node (ref "R2") (pin "2") (pinfunction "2_2") (pintype "passive"))
      (node (ref "R4") (pin "2") (pinfunction "2_2") (pintype "passive"))
    )
    (net (code "8") (name "Net-(IC2A-OUT)") (class "Default")
      (node (ref "IC2") (pin "1") (pinfunction "OUT_1") (pintype "output"))
      (node (ref "IC2") (pin "5") (pinfunction "+IN_5") (pintype "input"))
      (node (ref "R4") (pin "1") (pinfunction "1_1") (pintype "passive"))
    )
    (net (code "9") (name "Net-(IC2B--IN)") (class "Default")
      (node (ref "IC2") (pin "6") (pinfunction "-IN_6") (pintype "input"))
      (node (ref "R6") (pin "1") (pinfunction "1_1") (pintype "passive"))
      (node (ref "R7") (pin "2") (pinfunction "2_2") (pintype "passive"))
    )
    (net (code "10") (name "Net-(IC2B-OUT)") (class "Default")
      (node (ref "IC2") (pin "7") (pinfunction "OUT_7") (pintype "output"))
      (node (ref "R8") (pin "2") (pinfunction "2_2") (pintype "passive"))
    )
    (net (code "11") (name "Net-(IC5A-+IN)") (class "Default")
      (node (ref "IC5") (pin "3") (pinfunction "+IN_3") (pintype "input"))
      (node (ref "R28") (pin "2") (pinfunction "2_2") (pintype "passive"))
      (node (ref "R37") (pin "1") (pinfunction "1_1") (pintype "passive"))
      (node (ref "R39") (pin "1") (pinfunction "1_1") (pintype "passive"))
      (node (ref "T15") (pin "3") (pinfunction "S_3") (pintype "passive"))
    )
    (net (code "12") (name "Net-(IC5A--IN)") (class "Default")
      (node (ref "IC5") (pin "1") (pinfunction "OUT_1") (pintype "output"))
      (node (ref "IC5") (pin "2") (pinfunction "-IN_2") (pintype "input"))
      (node (ref "R29") (pin "1") (pinfunction "1_1") (pintype "passive"))
    )
    (net (code "13") (name "Net-(IC5B--IN)") (class "Default")
      (node (ref "IC5") (pin "6") (pinfunction "-IN_6") (pintype "input"))
      (node (ref "IC5") (pin "7") (pinfunction "OUT_7") (pintype "output"))
      (node (ref "R30") (pin "1") (pinfunction "1_1") (pintype "passive"))
    )
    (net (code "14") (name "Net-(IC6A-+IN)") (class "Default")
      (node (ref "IC6") (pin "3") (pinfunction "+IN_3") (pintype "input"))
      (node (ref "R30") (pin "2") (pinfunction "2_2") (pintype "passive"))
      (node (ref "R32") (pin "2") (pinfunction "2_2") (pintype "passive"))
    )
    (net (code "15") (name "Net-(IC6A--IN)") (class "Default")
      (node (ref "IC6") (pin "2") (pinfunction "-IN_2") (pintype "input"))
      (node (ref "R29") (pin "2") (pinfunction "2_2") (pintype "passive"))
      (node (ref "R31") (pin "2") (pinfunction "2_2") (pintype "passive"))
    )
    (net (code "16") (name "Net-(IC6A-OUT)") (class "Default")
      (node (ref "IC6") (pin "1") (pinfunction "OUT_1") (pintype "output"))
      (node (ref "IC6") (pin "5") (pinfunction "+IN_5") (pintype "input"))
      (node (ref "R31") (pin "1") (pinfunction "1_1") (pintype "passive"))
    )
    (net (code "17") (name "Net-(IC6B--IN)") (class "Default")
      (node (ref "IC6") (pin "6") (pinfunction "-IN_6") (pintype "input"))
      (node (ref "R33") (pin "2") (pinfunction "2_2") (pintype "passive"))
      (node (ref "R35") (pin "1") (pinfunction "1_1") (pintype "passive"))
    )
    (net (code "18") (name "Net-(IC6B-OUT)") (class "Default")
      (node (ref "IC6") (pin "7") (pinfunction "OUT_7") (pintype "output"))
      (node (ref "R34") (pin "2") (pinfunction "2_2") (pintype "passive"))
    )
    (net (code "19") (name "Net-(IC7A-+IN)") (class "Default")
      (node (ref "IC7") (pin "3") (pinfunction "+IN_3") (pintype "input"))
      (node (ref "R42") (pin "2") (pinfunction "2_2") (pintype "passive"))
      (node (ref "R51") (pin "1") (pinfunction "1_1") (pintype "passive"))
      (node (ref "R53") (pin "1") (pinfunction "1_1") (pintype "passive"))
      (node (ref "T20") (pin "3") (pinfunction "S_3") (pintype "passive"))
    )
    (net (code "20") (name "Net-(IC7A--IN)") (class "Default")
      (node (ref "IC7") (pin "1") (pinfunction "OUT_1") (pintype "output"))
      (node (ref "IC7") (pin "2") (pinfunction "-IN_2") (pintype "input"))
      (node (ref "R43") (pin "1") (pinfunction "1_1") (pintype "passive"))
    )
    (net (code "21") (name "Net-(IC7B--IN)") (class "Default")
      (node (ref "IC7") (pin "6") (pinfunction "-IN_6") (pintype "input"))
      (node (ref "IC7") (pin "7") (pinfunction "OUT_7") (pintype "output"))
      (node (ref "R44") (pin "1") (pinfunction "1_1") (pintype "passive"))
    )
    (net (code "22") (name "Net-(IC8A-+IN)") (class "Default")
      (node (ref "IC8") (pin "3") (pinfunction "+IN_3") (pintype "input"))
      (node (ref "R44") (pin "2") (pinfunction "2_2") (pintype "passive"))
      (node (ref "R46") (pin "2") (pinfunction "2_2") (pintype "passive"))
    )
    (net (code "23") (name "Net-(IC8A--IN)") (class "Default")
      (node (ref "IC8") (pin "2") (pinfunction "-IN_2") (pintype "input"))
      (node (ref "R43") (pin "2") (pinfunction "2_2") (pintype "passive"))
      (node (ref "R45") (pin "2") (pinfunction "2_2") (pintype "passive"))
    )
    (net (code "24") (name "Net-(IC8A-OUT)") (class "Default")
      (node (ref "IC8") (pin "1") (pinfunction "OUT_1") (pintype "output"))
      (node (ref "IC8") (pin "5") (pinfunction "+IN_5") (pintype "input"))
      (node (ref "R45") (pin "1") (pinfunction "1_1") (pintype "passive"))
    )
    (net (code "25") (name "Net-(IC8B--IN)") (class "Default")
      (node (ref "IC8") (pin "6") (pinfunction "-IN_6") (pintype "input"))
      (node (ref "R47") (pin "2") (pinfunction "2_2") (pintype "passive"))
      (node (ref "R49") (pin "1") (pinfunction "1_1") (pintype "passive"))
    )
    (net (code "26") (name "Net-(IC8B-OUT)") (class "Default")
      (node (ref "IC8") (pin "7") (pinfunction "OUT_7") (pintype "output"))
      (node (ref "R48") (pin "2") (pinfunction "2_2") (pintype "passive"))
    )
    (net (code "27") (name "Net-(IC9A-+IN)") (class "Default")
      (node (ref "IC9") (pin "3") (pinfunction "+IN_3") (pintype "input"))
      (node (ref "R56") (pin "2") (pinfunction "2_2") (pintype "passive"))
      (node (ref "R65") (pin "1") (pinfunction "1_1") (pintype "passive"))
      (node (ref "R68") (pin "1") (pinfunction "1_1") (pintype "passive"))
      (node (ref "T25") (pin "3") (pinfunction "S_3") (pintype "passive"))
    )
    (net (code "28") (name "Net-(IC9A--IN)") (class "Default")
      (node (ref "IC9") (pin "1") (pinfunction "OUT_1") (pintype "output"))
      (node (ref "IC9") (pin "2") (pinfunction "-IN_2") (pintype "input"))
      (node (ref "R57") (pin "1") (pinfunction "1_1") (pintype "passive"))
    )
    (net (code "29") (name "Net-(IC9B--IN)") (class "Default")
      (node (ref "IC9") (pin "6") (pinfunction "-IN_6") (pintype "input"))
      (node (ref "IC9") (pin "7") (pinfunction "OUT_7") (pintype "output"))
      (node (ref "R58") (pin "1") (pinfunction "1_1") (pintype "passive"))
    )
    (net (code "30") (name "Net-(IC10A-+IN)") (class "Default")
      (node (ref "IC10") (pin "3") (pinfunction "+IN_3") (pintype "input"))
      (node (ref "R58") (pin "2") (pinfunction "2_2") (pintype "passive"))
      (node (ref "R60") (pin "2") (pinfunction "2_2") (pintype "passive"))
    )
    (net (code "31") (name "Net-(IC10A--IN)") (class "Default")
      (node (ref "IC10") (pin "2") (pinfunction "-IN_2") (pintype "input"))
      (node (ref "R57") (pin "2") (pinfunction "2_2") (pintype "passive"))
      (node (ref "R59") (pin "2") (pinfunction "2_2") (pintype "passive"))
    )
    (net (code "32") (name "Net-(IC10A-OUT)") (class "Default")
      (node (ref "IC10") (pin "1") (pinfunction "OUT_1") (pintype "output"))
      (node (ref "IC10") (pin "5") (pinfunction "+IN_5") (pintype "input"))
      (node (ref "R59") (pin "1") (pinfunction "1_1") (pintype "passive"))
    )
    (net (code "33") (name "Net-(IC10B--IN)") (class "Default")
      (node (ref "IC10") (pin "6") (pinfunction "-IN_6") (pintype "input"))
      (node (ref "R61") (pin "2") (pinfunction "2_2") (pintype "passive"))
    )
    (net (code "34") (name "Net-(IC10B-OUT)") (class "Default")
      (node (ref "IC10") (pin "7") (pinfunction "OUT_7") (pintype "output"))
      (node (ref "R62") (pin "2") (pinfunction "2_2") (pintype "passive"))
    )
    (net (code "35") (name "Net-(IC13A-+IN)") (class "Default")
      (node (ref "IC13") (pin "3") (pinfunction "+IN_3") (pintype "input"))
      (node (ref "R86") (pin "2") (pinfunction "2_2") (pintype "passive"))
      (node (ref "R95") (pin "1") (pinfunction "1_1") (pintype "passive"))
      (node (ref "R97") (pin "1") (pinfunction "1_1") (pintype "passive"))
      (node (ref "T35") (pin "3") (pinfunction "S_3") (pintype "passive"))
    )
    (net (code "36") (name "Net-(IC13A--IN)") (class "Default")
      (node (ref "IC13") (pin "1") (pinfunction "OUT_1") (pintype "output"))
      (node (ref "IC13") (pin "2") (pinfunction "-IN_2") (pintype "input"))
      (node (ref "R87") (pin "1") (pinfunction "1_1") (pintype "passive"))
    )
    (net (code "37") (name "Net-(IC13B--IN)") (class "Default")
      (node (ref "IC13") (pin "6") (pinfunction "-IN_6") (pintype "input"))
      (node (ref "IC13") (pin "7") (pinfunction "OUT_7") (pintype "output"))
      (node (ref "R88") (pin "1") (pinfunction "1_1") (pintype "passive"))
    )
    (net (code "38") (name "Net-(IC14A-+IN)") (class "Default")
      (node (ref "IC14") (pin "3") (pinfunction "+IN_3") (pintype "input"))
      (node (ref "R88") (pin "2") (pinfunction "2_2") (pintype "passive"))
      (node (ref "R90") (pin "2") (pinfunction "2_2") (pintype "passive"))
    )
    (net (code "39") (name "Net-(IC14A--IN)") (class "Default")
      (node (ref "IC14") (pin "2") (pinfunction "-IN_2") (pintype "input"))
      (node (ref "R87") (pin "2") (pinfunction "2_2") (pintype "passive"))
      (node (ref "R89") (pin "2") (pinfunction "2_2") (pintype "passive"))
    )
    (net (code "40") (name "Net-(IC14A-OUT)") (class "Default")
      (node (ref "IC14") (pin "1") (pinfunction "OUT_1") (pintype "output"))
      (node (ref "IC14") (pin "5") (pinfunction "+IN_5") (pintype "input"))
      (node (ref "R89") (pin "1") (pinfunction "1_1") (pintype "passive"))
    )
    (net (code "41") (name "Net-(IC14B--IN)") (class "Default")
      (node (ref "IC14") (pin "6") (pinfunction "-IN_6") (pintype "input"))
      (node (ref "R91") (pin "2") (pinfunction "2_2") (pintype "passive"))
      (node (ref "R93") (pin "1") (pinfunction "1_1") (pintype "passive"))
    )
    (net (code "42") (name "Net-(IC14B-OUT)") (class "Default")
      (node (ref "IC14") (pin "7") (pinfunction "OUT_7") (pintype "output"))
      (node (ref "R92") (pin "2") (pinfunction "2_2") (pintype "passive"))
    )
    (net (code "43") (name "Net-(LED1-PadC)") (class "Default")
      (node (ref "LED1") (pin "C") (pinfunction "C_C") (pintype "passive"))
      (node (ref "R66") (pin "2") (pinfunction "2_2") (pintype "passive"))
    )
    (net (code "44") (name "Net-(LED2-PadC)") (class "Default")
      (node (ref "LED2") (pin "C") (pinfunction "C_C") (pintype "passive"))
      (node (ref "R14") (pin "2") (pinfunction "2_2") (pintype "passive"))
    )
    (net (code "45") (name "Net-(LED3-PadC)") (class "Default")
      (node (ref "LED3") (pin "C") (pinfunction "C_C") (pintype "passive"))
      (node (ref "R15") (pin "2") (pinfunction "2_2") (pintype "passive"))
    )
    (net (code "46") (name "Net-(LED4-PadC)") (class "Default")
      (node (ref "LED4") (pin "C") (pinfunction "C_C") (pintype "passive"))
      (node (ref "R16") (pin "2") (pinfunction "2_2") (pintype "passive"))
    )
    (net (code "47") (name "Net-(LED5-PadC)") (class "Default")
      (node (ref "LED5") (pin "C") (pinfunction "C_C") (pintype "passive"))
      (node (ref "R17") (pin "2") (pinfunction "2_2") (pintype "passive"))
    )
    (net (code "48") (name "Net-(T1-B)") (class "Default")
      (node (ref "R8") (pin "1") (pinfunction "1_1") (pintype "passive"))
      (node (ref "T1") (pin "1") (pinfunction "B_1") (pintype "passive"))
    )
    (net (code "49") (name "Net-(T1-C)") (class "Default")
      (node (ref "D1") (pin "A") (pinfunction "A_A") (pintype "passive"))
      (node (ref "R9") (pin "2") (pinfunction "2_2") (pintype "passive"))
      (node (ref "T1") (pin "3") (pinfunction "C_3") (pintype "passive"))
    )
    (net (code "50") (name "Net-(T2-B)") (class "Default")
      (node (ref "D1") (pin "C") (pinfunction "C_C") (pintype "passive"))
      (node (ref "R69") (pin "2") (pinfunction "2_2") (pintype "passive"))
      (node (ref "S1") (pin "3") (pinfunction "P$2_3") (pintype "passive"))
      (node (ref "S1") (pin "4") (pinfunction "P$2_4") (pintype "passive"))
      (node (ref "T2") (pin "1") (pinfunction "B_1") (pintype "passive"))
    )
    (net (code "51") (name "Net-(T2-C)") (class "Default")
      (node (ref "R11") (pin "2") (pinfunction "2_2") (pintype "passive"))
      (node (ref "T2") (pin "3") (pinfunction "C_3") (pintype "passive"))
      (node (ref "T5") (pin "1") (pinfunction "B_1") (pintype "passive"))
    )
    (net (code "52") (name "Net-(T2-E)") (class "Default")
      (node (ref "R12") (pin "2") (pinfunction "2_2") (pintype "passive"))
      (node (ref "T2") (pin "2") (pinfunction "E_2") (pintype "passive"))
      (node (ref "T4") (pin "3") (pinfunction "C_3") (pintype "passive"))
    )
    (net (code "53") (name "Net-(T3-G)") (class "Default")
      (node (ref "R10") (pin "2") (pinfunction "2_2") (pintype "passive"))
      (node (ref "T3") (pin "1") (pinfunction "G_1") (pintype "passive"))
      (node (ref "T5") (pin "3") (pinfunction "C_3") (pintype "passive"))
    )
    (net (code "54") (name "Net-(T4-B)") (class "Default")
      (node (ref "C3") (pin "1") (pinfunction "1_1") (pintype "passive"))
      (node (ref "R13") (pin "2") (pinfunction "2_2") (pintype "passive"))
      (node (ref "T4") (pin "1") (pinfunction "B_1") (pintype "passive"))
    )
    (net (code "55") (name "Net-(T11-B)") (class "Default")
      (node (ref "R34") (pin "1") (pinfunction "1_1") (pintype "passive"))
      (node (ref "T11") (pin "1") (pinfunction "B_1") (pintype "passive"))
    )
    (net (code "56") (name "Net-(T11-C)") (class "Default")
      (node (ref "D3") (pin "A") (pinfunction "A_A") (pintype "passive"))
      (node (ref "R36") (pin "2") (pinfunction "2_2") (pintype "passive"))
      (node (ref "T11") (pin "3") (pinfunction "C_3") (pintype "passive"))
    )
    (net (code "57") (name "Net-(T12-B)") (class "Default")
      (node (ref "C9") (pin "1") (pinfunction "1_1") (pintype "passive"))
      (node (ref "R40") (pin "2") (pinfunction "2_2") (pintype "passive"))
      (node (ref "T12") (pin "1") (pinfunction "B_1") (pintype "passive"))
    )
    (net (code "58") (name "Net-(T12-C)") (class "Default")
      (node (ref "R39") (pin "2") (pinfunction "2_2") (pintype "passive"))
      (node (ref "T12") (pin "3") (pinfunction "C_3") (pintype "passive"))
      (node (ref "T13") (pin "2") (pinfunction "E_2") (pintype "passive"))
    )
    (net (code "59") (name "Net-(T13-B)") (class "Default")
      (node (ref "D3") (pin "C") (pinfunction "C_C") (pintype "passive"))
      (node (ref "R41") (pin "2") (pinfunction "2_2") (pintype "passive"))
      (node (ref "S3") (pin "3") (pinfunction "P$2_3") (pintype "passive"))
      (node (ref "S3") (pin "4") (pinfunction "P$2_4") (pintype "passive"))
      (node (ref "T13") (pin "1") (pinfunction "B_1") (pintype "passive"))
    )
    (net (code "60") (name "Net-(T13-C)") (class "Default")
      (node (ref "R38") (pin "2") (pinfunction "2_2") (pintype "passive"))
      (node (ref "T13") (pin "3") (pinfunction "C_3") (pintype "passive"))
      (node (ref "T14") (pin "1") (pinfunction "B_1") (pintype "passive"))
    )
    (net (code "61") (name "Net-(T14-C)") (class "Default")
      (node (ref "R37") (pin "2") (pinfunction "2_2") (pintype "passive"))
      (node (ref "T14") (pin "3") (pinfunction "C_3") (pintype "passive"))
      (node (ref "T15") (pin "1") (pinfunction "G_1") (pintype "passive"))
    )
    (net (code "62") (name "Net-(T16-B)") (class "Default")
      (node (ref "R48") (pin "1") (pinfunction "1_1") (pintype "passive"))
      (node (ref "T16") (pin "1") (pinfunction "B_1") (pintype "passive"))
    )
    (net (code "63") (name "Net-(T16-C)") (class "Default")
      (node (ref "D4") (pin "A") (pinfunction "A_A") (pintype "passive"))
      (node (ref "R50") (pin "2") (pinfunction "2_2") (pintype "passive"))
      (node (ref "T16") (pin "3") (pinfunction "C_3") (pintype "passive"))
    )
    (net (code "64") (name "Net-(T17-B)") (class "Default")
      (node (ref "C12") (pin "1") (pinfunction "1_1") (pintype "passive"))
      (node (ref "R54") (pin "2") (pinfunction "2_2") (pintype "passive"))
      (node (ref "T17") (pin "1") (pinfunction "B_1") (pintype "passive"))
    )
    (net (code "65") (name "Net-(T17-C)") (class "Default")
      (node (ref "R53") (pin "2") (pinfunction "2_2") (pintype "passive"))
      (node (ref "T17") (pin "3") (pinfunction "C_3") (pintype "passive"))
      (node (ref "T18") (pin "2") (pinfunction "E_2") (pintype "passive"))
    )
    (net (code "66") (name "Net-(T18-B)") (class "Default")
      (node (ref "D4") (pin "C") (pinfunction "C_C") (pintype "passive"))
      (node (ref "R55") (pin "2") (pinfunction "2_2") (pintype "passive"))
      (node (ref "S4") (pin "3") (pinfunction "P$2_3") (pintype "passive"))
      (node (ref "S4") (pin "4") (pinfunction "P$2_4") (pintype "passive"))
      (node (ref "T18") (pin "1") (pinfunction "B_1") (pintype "passive"))
    )
    (net (code "67") (name "Net-(T18-C)") (class "Default")
      (node (ref "R52") (pin "2") (pinfunction "2_2") (pintype "passive"))
      (node (ref "T18") (pin "3") (pinfunction "C_3") (pintype "passive"))
      (node (ref "T19") (pin "1") (pinfunction "B_1") (pintype "passive"))
    )
    (net (code "68") (name "Net-(T19-C)") (class "Default")
      (node (ref "R51") (pin "2") (pinfunction "2_2") (pintype "passive"))
      (node (ref "T19") (pin "3") (pinfunction "C_3") (pintype "passive"))
      (node (ref "T20") (pin "1") (pinfunction "G_1") (pintype "passive"))
    )
    (net (code "69") (name "Net-(T21-B)") (class "Default")
      (node (ref "R62") (pin "1") (pinfunction "1_1") (pintype "passive"))
      (node (ref "T21") (pin "1") (pinfunction "B_1") (pintype "passive"))
    )
    (net (code "70") (name "Net-(T21-C)") (class "Default")
      (node (ref "D5") (pin "A") (pinfunction "A_A") (pintype "passive"))
      (node (ref "R64") (pin "2") (pinfunction "2_2") (pintype "passive"))
      (node (ref "T21") (pin "3") (pinfunction "C_3") (pintype "passive"))
    )
    (net (code "71") (name "Net-(T22-B)") (class "Default")
      (node (ref "C15") (pin "1") (pinfunction "1_1") (pintype "passive"))
      (node (ref "R70") (pin "2") (pinfunction "2_2") (pintype "passive"))
      (node (ref "T22") (pin "1") (pinfunction "B_1") (pintype "passive"))
    )
    (net (code "72") (name "Net-(T22-C)") (class "Default")
      (node (ref "R68") (pin "2") (pinfunction "2_2") (pintype "passive"))
      (node (ref "T22") (pin "3") (pinfunction "C_3") (pintype "passive"))
      (node (ref "T23") (pin "2") (pinfunction "E_2") (pintype "passive"))
    )
    (net (code "73") (name "Net-(T23-B)") (class "Default")
      (node (ref "D5") (pin "C") (pinfunction "C_C") (pintype "passive"))
      (node (ref "R71") (pin "2") (pinfunction "2_2") (pintype "passive"))
      (node (ref "S5") (pin "3") (pinfunction "P$2_3") (pintype "passive"))
      (node (ref "S5") (pin "4") (pinfunction "P$2_4") (pintype "passive"))
      (node (ref "T23") (pin "1") (pinfunction "B_1") (pintype "passive"))
    )
    (net (code "74") (name "Net-(T23-C)") (class "Default")
      (node (ref "R67") (pin "2") (pinfunction "2_2") (pintype "passive"))
      (node (ref "T23") (pin "3") (pinfunction "C_3") (pintype "passive"))
      (node (ref "T24") (pin "1") (pinfunction "B_1") (pintype "passive"))
    )
    (net (code "75") (name "Net-(T24-C)") (class "Default")
      (node (ref "R65") (pin "2") (pinfunction "2_2") (pintype "passive"))
      (node (ref "T24") (pin "3") (pinfunction "C_3") (pintype "passive"))
      (node (ref "T25") (pin "1") (pinfunction "G_1") (pintype "passive"))
    )
    (net (code "76") (name "Net-(T31-B)") (class "Default")
      (node (ref "R92") (pin "1") (pinfunction "1_1") (pintype "passive"))
      (node (ref "T31") (pin "1") (pinfunction "B_1") (pintype "passive"))
    )
    (net (code "77") (name "Net-(T31-C)") (class "Default")
      (node (ref "D7") (pin "A") (pinfunction "A_A") (pintype "passive"))
      (node (ref "R94") (pin "2") (pinfunction "2_2") (pintype "passive"))
      (node (ref "T31") (pin "3") (pinfunction "C_3") (pintype "passive"))
    )
    (net (code "78") (name "Net-(T32-B)") (class "Default")
      (node (ref "C21") (pin "1") (pinfunction "1_1") (pintype "passive"))
      (node (ref "R98") (pin "2") (pinfunction "2_2") (pintype "passive"))
      (node (ref "T32") (pin "1") (pinfunction "B_1") (pintype "passive"))
    )
    (net (code "79") (name "Net-(T32-C)") (class "Default")
      (node (ref "R97") (pin "2") (pinfunction "2_2") (pintype "passive"))
      (node (ref "T32") (pin "3") (pinfunction "C_3") (pintype "passive"))
      (node (ref "T33") (pin "2") (pinfunction "E_2") (pintype "passive"))
    )
    (net (code "80") (name "Net-(T33-B)") (class "Default")
      (node (ref "D7") (pin "C") (pinfunction "C_C") (pintype "passive"))
      (node (ref "R99") (pin "2") (pinfunction "2_2") (pintype "passive"))
      (node (ref "S7") (pin "3") (pinfunction "P$2_3") (pintype "passive"))
      (node (ref "S7") (pin "4") (pinfunction "P$2_4") (pintype "passive"))
      (node (ref "T33") (pin "1") (pinfunction "B_1") (pintype "passive"))
    )
    (net (code "81") (name "Net-(T33-C)") (class "Default")
      (node (ref "R96") (pin "2") (pinfunction "2_2") (pintype "passive"))
      (node (ref "T33") (pin "3") (pinfunction "C_3") (pintype "passive"))
      (node (ref "T34") (pin "1") (pinfunction "B_1") (pintype "passive"))
    )
    (net (code "82") (name "Net-(T34-C)") (class "Default")
      (node (ref "R95") (pin "2") (pinfunction "2_2") (pintype "passive"))
      (node (ref "T34") (pin "3") (pinfunction "C_3") (pintype "passive"))
      (node (ref "T35") (pin "1") (pinfunction "G_1") (pintype "passive"))
    )
    (net (code "83") (name "OUT1") (class "Default")
      (node (ref "J2") (pin "17") (pinfunction "9_1_17") (pintype "passive"))
      (node (ref "J2") (pin "18") (pinfunction "9_2_18") (pintype "passive"))
      (node (ref "LED1") (pin "A") (pinfunction "A_A") (pintype "passive"))
      (node (ref "R11") (pin "1") (pinfunction "1_1") (pintype "passive"))
      (node (ref "R13") (pin "1") (pinfunction "1_1") (pintype "passive"))
      (node (ref "T3") (pin "4") (pinfunction "D_4") (pintype "passive"))
    )
    (net (code "84") (name "OUT2") (class "Default")
      (node (ref "J2") (pin "13") (pinfunction "7_1_13") (pintype "passive"))
      (node (ref "J2") (pin "14") (pinfunction "7_2_14") (pintype "passive"))
      (node (ref "LED2") (pin "A") (pinfunction "A_A") (pintype "passive"))
      (node (ref "R38") (pin "1") (pinfunction "1_1") (pintype "passive"))
      (node (ref "R40") (pin "1") (pinfunction "1_1") (pintype "passive"))
      (node (ref "T15") (pin "4") (pinfunction "D_4") (pintype "passive"))
    )
    (net (code "85") (name "OUT3") (class "Default")
      (node (ref "J2") (pin "10") (pinfunction "5_2_10") (pintype "passive"))
      (node (ref "J2") (pin "9") (pinfunction "5_1_9") (pintype "passive"))
      (node (ref "LED3") (pin "A") (pinfunction "A_A") (pintype "passive"))
      (node (ref "R52") (pin "1") (pinfunction "1_1") (pintype "passive"))
      (node (ref "R54") (pin "1") (pinfunction "1_1") (pintype "passive"))
      (node (ref "T20") (pin "4") (pinfunction "D_4") (pintype "passive"))
    )
    (net (code "86") (name "OUT4") (class "Default")
      (node (ref "J2") (pin "5") (pinfunction "3_1_5") (pintype "passive"))
      (node (ref "J2") (pin "6") (pinfunction "3_2_6") (pintype "passive"))
      (node (ref "LED4") (pin "A") (pinfunction "A_A") (pintype "passive"))
      (node (ref "R67") (pin "1") (pinfunction "1_1") (pintype "passive"))
      (node (ref "R70") (pin "1") (pinfunction "1_1") (pintype "passive"))
      (node (ref "T25") (pin "4") (pinfunction "D_4") (pintype "passive"))
    )
    (net (code "87") (name "OUT5") (class "Default")
      (node (ref "J2") (pin "1") (pinfunction "1_1_1") (pintype "passive"))
      (node (ref "J2") (pin "2") (pinfunction "1_2_2") (pintype "passive"))
      (node (ref "LED5") (pin "A") (pinfunction "A_A") (pintype "passive"))
      (node (ref "R96") (pin "1") (pinfunction "1_1") (pintype "passive"))
      (node (ref "R98") (pin "1") (pinfunction "1_1") (pintype "passive"))
      (node (ref "T35") (pin "4") (pinfunction "D_4") (pintype "passive"))
    )
  )
)
